# InverterConnectors.net
KiCad netlist of a schematic drawn in Altium Designer
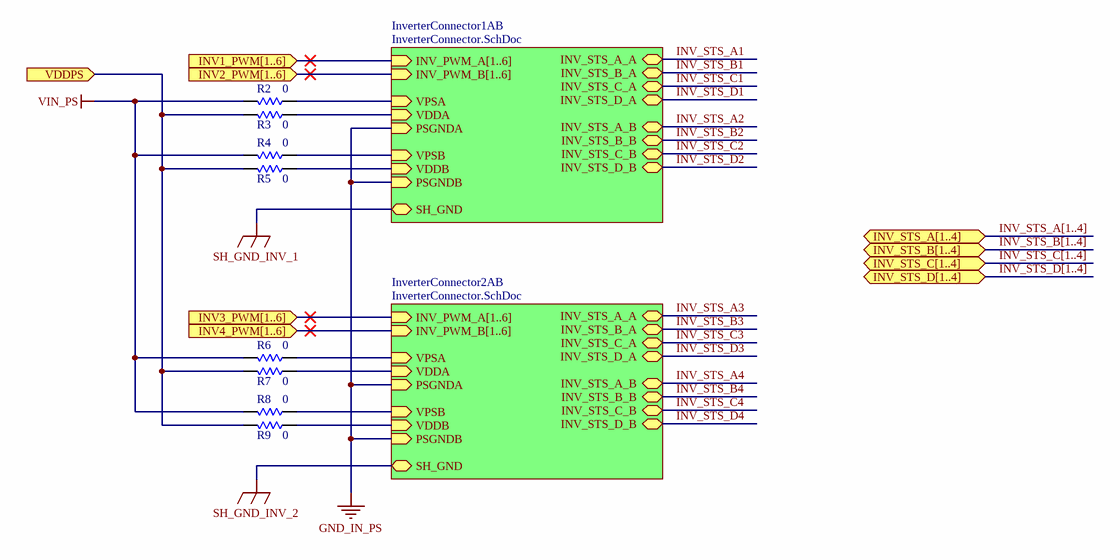
[diagram p0: InverterConnectors.SchDoc]

(export (version "E")
  (design (tool "Eeschema 10.0.6"))
  (components
    (comp (ref "R2")
      (value "0")
      (footprint "AMDC:1206-RES")
      (description "Resistor")
      (libsource (lib "AMDC") (part "Resistor"))
    )
    (comp (ref "R3")
      (value "0")
      (footprint "AMDC:1206-RES")
      (description "Resistor")
      (libsource (lib "AMDC") (part "Resistor"))
    )
    (comp (ref "R4")
      (value "0")
      (footprint "AMDC:1206-RES")
      (description "Resistor")
      (libsource (lib "AMDC") (part "Resistor"))
    )
    (comp (ref "R5")
      (value "0")
      (footprint "AMDC:1206-RES")
      (description "Resistor")
      (libsource (lib "AMDC") (part "Resistor"))
    )
    (comp (ref "R6")
      (value "0")
      (footprint "AMDC:1206-RES")
      (description "Resistor")
      (libsource (lib "AMDC") (part "Resistor"))
    )
    (comp (ref "R7")
      (value "0")
      (footprint "AMDC:1206-RES")
      (description "Resistor")
      (libsource (lib "AMDC") (part "Resistor"))
    )
    (comp (ref "R8")
      (value "0")
      (footprint "AMDC:1206-RES")
      (description "Resistor")
      (libsource (lib "AMDC") (part "Resistor"))
    )
    (comp (ref "R9")
      (value "0")
      (footprint "AMDC:1206-RES")
      (description "Resistor")
      (libsource (lib "AMDC") (part "Resistor"))
    )
  )
  (nets
    (net (code "49") (name "/VDDA") (class "Default")
      (node (ref "R3") (pin "1") (pinfunction "1_1") (pintype "passive"))
    )
    (net (code "50") (name "/VDDA_1") (class "Default")
      (node (ref "R7") (pin "1") (pinfunction "1_1") (pintype "passive"))
    )
    (net (code "51") (name "/VDDB") (class "Default")
      (node (ref "R5") (pin "1") (pinfunction "1_1") (pintype "passive"))
    )
    (net (code "52") (name "/VDDB_1") (class "Default")
      (node (ref "R9") (pin "1") (pinfunction "1_1") (pintype "passive"))
    )
    (net (code "53") (name "/VDDPS") (class "Default")
      (node (ref "R3") (pin "2") (pinfunction "2_2") (pintype "passive"))
      (node (ref "R5") (pin "2") (pinfunction "2_2") (pintype "passive"))
      (node (ref "R7") (pin "2") (pinfunction "2_2") (pintype "passive"))
      (node (ref "R9") (pin "2") (pinfunction "2_2") (pintype "passive"))
    )
    (net (code "54") (name "/VPSA") (class "Default")
      (node (ref "R2") (pin "1") (pinfunction "1_1") (pintype "passive"))
    )
    (net (code "55") (name "/VPSA_1") (class "Default")
      (node (ref "R6") (pin "1") (pinfunction "1_1") (pintype "passive"))
    )
    (net (code "56") (name "/VPSB") (class "Default")
      (node (ref "R4") (pin "1") (pinfunction "1_1") (pintype "passive"))
    )
    (net (code "57") (name "/VPSB_1") (class "Default")
      (node (ref "R8") (pin "1") (pinfunction "1_1") (pintype "passive"))
    )
    (net (code "61") (name "VIN_PS") (class "Default")
      (node (ref "R2") (pin "2") (pinfunction "2_2") (pintype "passive"))
      (node (ref "R4") (pin "2") (pinfunction "2_2") (pintype "passive"))
      (node (ref "R6") (pin "2") (pinfunction "2_2") (pintype "passive"))
      (node (ref "R8") (pin "2") (pinfunction "2_2") (pintype "passive"))
    )
  )
)
